# Voltmeter_Before.net
KiCad netlist of a schematic drawn in Altium Designer
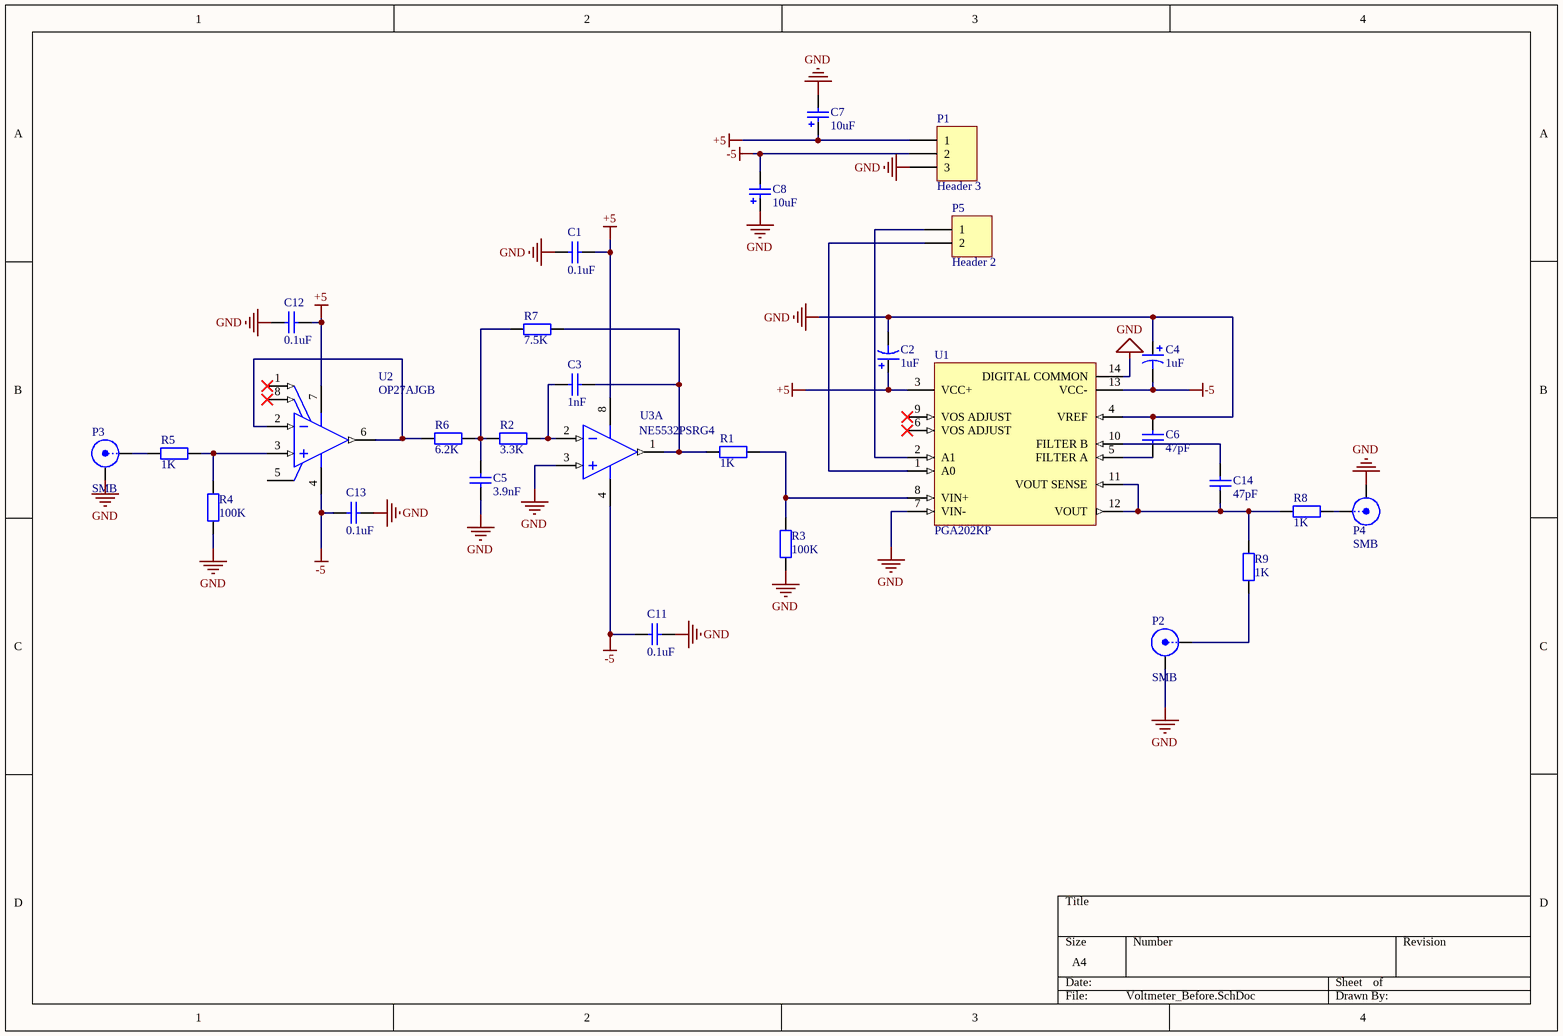
[diagram p0: Voltmeter_Before.SchDoc]

(export (version "E")
  (design (tool "Eeschema 10.0.6"))
  (components
    (comp (ref "C1")
      (value "0.1uF")
      (footprint "C0805")
      (description "Capacitor (Semiconductor SIM Model)")
      (fields (field (name "Comment") "Cap Semi") (field (name "PUBLISHER") "Altium Limited"))
      (libsource (lib "Miscellaneous Devices") (part "Cap Semi"))
    )
    (comp (ref "C2")
      (value "1uF")
      (footprint "C0805")
      (description "Polarized Capacitor (Surface Mount)")
      (fields (field (name "Comment") "Cap Pol3") (field (name "PUBLISHER") "Altium Limited"))
      (libsource (lib "Miscellaneous Devices") (part "Cap Pol3"))
    )
    (comp (ref "C3")
      (value "1nF")
      (footprint "C0805")
      (description "Capacitor (Semiconductor SIM Model)")
      (fields (field (name "Comment") "Cap Semi") (field (name "PUBLISHER") "Altium Limited"))
      (libsource (lib "Miscellaneous Devices") (part "Cap Semi"))
    )
    (comp (ref "C4")
      (value "1uF")
      (footprint "C0805")
      (description "Polarized Capacitor (Surface Mount)")
      (fields (field (name "Comment") "Cap Pol3") (field (name "PUBLISHER") "Altium Limited"))
      (libsource (lib "Miscellaneous Devices") (part "Cap Pol3"))
    )
    (comp (ref "C5")
      (value "3.9nF")
      (footprint "C0805")
      (description "Capacitor (Semiconductor SIM Model)")
      (fields (field (name "Comment") "Cap Semi") (field (name "PUBLISHER") "Altium Limited"))
      (libsource (lib "Miscellaneous Devices") (part "Cap Semi"))
    )
    (comp (ref "C6")
      (value "47pF")
      (footprint "C0805")
      (description "Capacitor (Semiconductor SIM Model)")
      (fields (field (name "Comment") "Cap Semi") (field (name "PUBLISHER") "Altium Limited"))
      (libsource (lib "Miscellaneous Devices") (part "Cap Semi"))
    )
    (comp (ref "C7")
      (value "10uF")
      (footprint "C0805")
      (description "Polarized Capacitor (Axial)")
      (fields (field (name "Comment") "Cap Pol2") (field (name "PUBLISHER") "Altium Limited"))
      (libsource (lib "Miscellaneous Devices") (part "Cap Pol2"))
    )
    (comp (ref "C8")
      (value "10uF")
      (footprint "C0805")
      (description "Polarized Capacitor (Axial)")
      (fields (field (name "Comment") "Cap Pol2") (field (name "PUBLISHER") "Altium Limited"))
      (libsource (lib "Miscellaneous Devices") (part "Cap Pol2"))
    )
    (comp (ref "C11")
      (value "0.1uF")
      (footprint "C0805")
      (description "Capacitor (Semiconductor SIM Model)")
      (fields (field (name "Comment") "Cap Semi") (field (name "PUBLISHER") "Altium Limited"))
      (libsource (lib "Miscellaneous Devices") (part "Cap Semi"))
    )
    (comp (ref "C12")
      (value "0.1uF")
      (footprint "C0805")
      (description "Capacitor (Semiconductor SIM Model)")
      (fields (field (name "Comment") "Cap Semi") (field (name "PUBLISHER") "Altium Limited"))
      (libsource (lib "Miscellaneous Devices") (part "Cap Semi"))
    )
    (comp (ref "C13")
      (value "0.1uF")
      (footprint "C0805")
      (description "Capacitor (Semiconductor SIM Model)")
      (fields (field (name "Comment") "Cap Semi") (field (name "PUBLISHER") "Altium Limited"))
      (libsource (lib "Miscellaneous Devices") (part "Cap Semi"))
    )
    (comp (ref "C14")
      (value "47pF")
      (footprint "C0805")
      (description "Capacitor (Semiconductor SIM Model)")
      (fields (field (name "Comment") "Cap Semi") (field (name "PUBLISHER") "Altium Limited"))
      (libsource (lib "Miscellaneous Devices") (part "Cap Semi"))
    )
    (comp (ref "P1")
      (value "Header 3")
      (footprint "HDR1X3")
      (description "Header, 3-Pin")
      (fields (field (name "PUBLISHER") "Altium Limited"))
      (libsource (lib "Miscellaneous Connectors") (part "Header 3"))
    )
    (comp (ref "P2")
      (value "SMB")
      (footprint "SMB_V-RJ45")
      (description "SMB Straight Connector")
      (fields (field (name "PUBLISHER") "Altium Limited"))
      (libsource (lib "Miscellaneous Connectors") (part "SMB"))
    )
    (comp (ref "P3")
      (value "SMB")
      (footprint "SMB_V-RJ45")
      (description "SMB Straight Connector")
      (fields (field (name "PUBLISHER") "Altium Limited"))
      (libsource (lib "Miscellaneous Connectors") (part "SMB"))
    )
    (comp (ref "P4")
      (value "SMB")
      (footprint "SMB_V-RJ45")
      (description "SMB Straight Connector")
      (fields (field (name "PUBLISHER") "Altium Limited"))
      (libsource (lib "Miscellaneous Connectors") (part "SMB"))
    )
    (comp (ref "P5")
      (value "Header 2")
      (footprint "HDR1X2")
      (description "Header, 2-Pin")
      (fields (field (name "PUBLISHER") "Altium Limited"))
      (libsource (lib "Miscellaneous Connectors") (part "Header 2"))
    )
    (comp (ref "R1")
      (value "1K")
      (footprint "C0805")
      (description "Resistor")
      (fields (field (name "Comment") "Res2") (field (name "PUBLISHER") "Altium Limited"))
      (libsource (lib "") (part "Res2_1"))
    )
    (comp (ref "R2")
      (value "3.3K")
      (footprint "C0805")
      (description "Resistor")
      (fields (field (name "Comment") "Res2") (field (name "PUBLISHER") "Altium Limited"))
      (libsource (lib "") (part "Res2_1"))
    )
    (comp (ref "R3")
      (value "100K")
      (footprint "C0805")
      (description "Resistor")
      (fields (field (name "Comment") "Res2") (field (name "PUBLISHER") "Altium Limited"))
      (libsource (lib "Miscellaneous Devices") (part "Res2"))
    )
    (comp (ref "R4")
      (value "100K")
      (footprint "C0805")
      (description "Resistor")
      (fields (field (name "Comment") "Res2") (field (name "PUBLISHER") "Altium Limited"))
      (libsource (lib "Miscellaneous Devices") (part "Res2"))
    )
    (comp (ref "R5")
      (value "1K")
      (footprint "C0805")
      (description "Resistor")
      (fields (field (name "Comment") "Res2") (field (name "PUBLISHER") "Altium Limited"))
      (libsource (lib "") (part "Res2_1"))
    )
    (comp (ref "R6")
      (value "6.2K")
      (footprint "C0805")
      (description "Resistor")
      (fields (field (name "Comment") "Res2") (field (name "PUBLISHER") "Altium Limited"))
      (libsource (lib "") (part "Res2_1"))
    )
    (comp (ref "R7")
      (value "7.5K")
      (footprint "C0805")
      (description "Resistor")
      (fields (field (name "Comment") "Res2") (field (name "PUBLISHER") "Altium Limited"))
      (libsource (lib "") (part "Res2_2"))
    )
    (comp (ref "R8")
      (value "1K")
      (footprint "C0805")
      (description "Resistor")
      (fields (field (name "Comment") "Res2") (field (name "PUBLISHER") "Altium Limited"))
      (libsource (lib "") (part "Res2_1"))
    )
    (comp (ref "R9")
      (value "1K")
      (footprint "C0805")
      (description "Resistor")
      (fields (field (name "Comment") "Res2") (field (name "PUBLISHER") "Altium Limited"))
      (libsource (lib "Miscellaneous Devices") (part "Res2"))
    )
    (comp (ref "U1")
      (value "PGA202KP")
      (footprint "TI-N14")
      (fields (field (name "MANUFACTURER") "Texas Instruments"))
      (libsource (lib "TI Amplifiers and Linear PGA-VGA") (part "PGA202KP"))
    )
    (comp (ref "U2")
      (value "OP27AJGB")
      (footprint "TI-JG8")
      (description "Low-Noise Precision High-Speed Operational Amplifier, 8 to 44 V, -55 to 125 degC, 8-pin DIP (JG8)")
      (fields (field (name "MANUFACTURER") "Texas Instruments"))
      (libsource (lib "TI Amplifiers and Linear Operational Amplifier Precision Amplifier Part One") (part "OP27AJGB"))
    )
    (comp (ref "U3")
      (value "NE5532PSRG4")
      (footprint "DIP-8")
      (fields (field (name "MANUFACTURER") "Texas Instruments"))
      (libsource (lib "TI Amplifiers and Linear Operational Amplifier General Purpose") (part "NE5532PSRG4"))
    )
  )
  (nets
    (net (code "1") (name "+5") (class "Default")
      (node (ref "C1") (pin "1") (pinfunction "1_1") (pintype "passive"))
      (node (ref "C12") (pin "2") (pinfunction "2_2") (pintype "passive"))
      (node (ref "C2") (pin "1") (pinfunction "1_1") (pintype "passive"))
      (node (ref "C7") (pin "1") (pinfunction "1_1") (pintype "passive"))
      (node (ref "P1") (pin "1") (pinfunction "1_1") (pintype "passive"))
      (node (ref "U1") (pin "3") (pinfunction "VCC+_3") (pintype "power_in"))
      (node (ref "U2") (pin "7") (pinfunction "VCC+_7") (pintype "power_in"))
      (node (ref "U3") (pin "8") (pinfunction "VCC+_8") (pintype "power_in"))
    )
    (net (code "2") (name "-5") (class "Default")
      (node (ref "C11") (pin "2") (pinfunction "2_2") (pintype "passive"))
      (node (ref "C13") (pin "1") (pinfunction "1_1") (pintype "passive"))
      (node (ref "C4") (pin "2") (pinfunction "2_2") (pintype "passive"))
      (node (ref "C8") (pin "2") (pinfunction "2_2") (pintype "passive"))
      (node (ref "P1") (pin "2") (pinfunction "2_2") (pintype "passive"))
      (node (ref "U1") (pin "13") (pinfunction "VCC-_13") (pintype "power_in"))
      (node (ref "U2") (pin "4") (pinfunction "VCC-_4") (pintype "power_in"))
      (node (ref "U3") (pin "4") (pinfunction "VCC-_4") (pintype "power_in"))
    )
    (net (code "3") (name "GND") (class "Default")
      (node (ref "C1") (pin "2") (pinfunction "2_2") (pintype "passive"))
      (node (ref "C11") (pin "1") (pinfunction "1_1") (pintype "passive"))
      (node (ref "C12") (pin "1") (pinfunction "1_1") (pintype "passive"))
      (node (ref "C13") (pin "2") (pinfunction "2_2") (pintype "passive"))
      (node (ref "C2") (pin "2") (pinfunction "2_2") (pintype "passive"))
      (node (ref "C4") (pin "1") (pinfunction "1_1") (pintype "passive"))
      (node (ref "C5") (pin "1") (pinfunction "1_1") (pintype "passive"))
      (node (ref "C6") (pin "2") (pinfunction "2_2") (pintype "passive"))
      (node (ref "C7") (pin "2") (pinfunction "2_2") (pintype "passive"))
      (node (ref "C8") (pin "1") (pinfunction "1_1") (pintype "passive"))
      (node (ref "P1") (pin "3") (pinfunction "3_3") (pintype "passive"))
      (node (ref "P2") (pin "2") (pinfunction "Y_2") (pintype "passive"))
      (node (ref "P3") (pin "2") (pinfunction "Y_2") (pintype "passive"))
      (node (ref "P4") (pin "2") (pinfunction "Y_2") (pintype "passive"))
      (node (ref "R3") (pin "1") (pinfunction "1_1") (pintype "passive"))
      (node (ref "R4") (pin "1") (pinfunction "1_1") (pintype "passive"))
      (node (ref "U1") (pin "14") (pinfunction "DIGITAL_COMMON_14") (pintype "power_in"))
      (node (ref "U1") (pin "4") (pinfunction "VREF_4") (pintype "input"))
      (node (ref "U1") (pin "7") (pinfunction "VIN-_7") (pintype "input"))
      (node (ref "U3") (pin "3") (pinfunction "IN1+_3") (pintype "input"))
    )
    (net (code "4") (name "Net-(C5-Pad2)") (class "Default")
      (node (ref "C5") (pin "2") (pinfunction "2_2") (pintype "passive"))
      (node (ref "R2") (pin "1") (pinfunction "1_1") (pintype "passive"))
      (node (ref "R6") (pin "2") (pinfunction "2_2") (pintype "passive"))
      (node (ref "R7") (pin "2") (pinfunction "2_2") (pintype "passive"))
    )
    (net (code "5") (name "Net-(P2-X)") (class "Default")
      (node (ref "P2") (pin "1") (pinfunction "X_1") (pintype "passive"))
      (node (ref "R9") (pin "1") (pinfunction "1_1") (pintype "passive"))
    )
    (net (code "6") (name "Net-(P3-X)") (class "Default")
      (node (ref "P3") (pin "1") (pinfunction "X_1") (pintype "passive"))
      (node (ref "R5") (pin "1") (pinfunction "1_1") (pintype "passive"))
    )
    (net (code "7") (name "Net-(P4-X)") (class "Default")
      (node (ref "P4") (pin "1") (pinfunction "X_1") (pintype "passive"))
      (node (ref "R8") (pin "2") (pinfunction "2_2") (pintype "passive"))
    )
    (net (code "8") (name "Net-(U1-A0)") (class "Default")
      (node (ref "P5") (pin "2") (pinfunction "2_2") (pintype "passive"))
      (node (ref "U1") (pin "1") (pinfunction "A0_1") (pintype "input"))
    )
    (net (code "9") (name "Net-(U1-A1)") (class "Default")
      (node (ref "P5") (pin "1") (pinfunction "1_1") (pintype "passive"))
      (node (ref "U1") (pin "2") (pinfunction "A1_2") (pintype "input"))
    )
    (net (code "10") (name "Net-(U1-FILTER_A)") (class "Default")
      (node (ref "C6") (pin "1") (pinfunction "1_1") (pintype "passive"))
      (node (ref "U1") (pin "5") (pinfunction "FILTER_A_5") (pintype "input"))
    )
    (net (code "11") (name "Net-(U1-FILTER_B)") (class "Default")
      (node (ref "C14") (pin "2") (pinfunction "2_2") (pintype "passive"))
      (node (ref "U1") (pin "10") (pinfunction "FILTER_B_10") (pintype "input"))
    )
    (net (code "12") (name "Net-(U1-VIN+)") (class "Default")
      (node (ref "R1") (pin "2") (pinfunction "2_2") (pintype "passive"))
      (node (ref "R3") (pin "2") (pinfunction "2_2") (pintype "passive"))
      (node (ref "U1") (pin "8") (pinfunction "VIN+_8") (pintype "input"))
    )
    (net (code "13") (name "Net-(U1-VOUT)") (class "Default")
      (node (ref "C14") (pin "1") (pinfunction "1_1") (pintype "passive"))
      (node (ref "R8") (pin "1") (pinfunction "1_1") (pintype "passive"))
      (node (ref "R9") (pin "2") (pinfunction "2_2") (pintype "passive"))
      (node (ref "U1") (pin "11") (pinfunction "VOUT_SENSE_11") (pintype "input"))
      (node (ref "U1") (pin "12") (pinfunction "VOUT_12") (pintype "output"))
    )
    (net (code "14") (name "Net-(U2-IN+)") (class "Default")
      (node (ref "R4") (pin "2") (pinfunction "2_2") (pintype "passive"))
      (node (ref "R5") (pin "2") (pinfunction "2_2") (pintype "passive"))
      (node (ref "U2") (pin "3") (pinfunction "IN+_3") (pintype "input"))
    )
    (net (code "15") (name "Net-(U2-IN-)") (class "Default")
      (node (ref "R6") (pin "1") (pinfunction "1_1") (pintype "passive"))
      (node (ref "U2") (pin "2") (pinfunction "IN-_2") (pintype "input"))
      (node (ref "U2") (pin "6") (pinfunction "OUT_6") (pintype "output"))
    )
    (net (code "16") (name "Net-(U3A-IN1-)") (class "Default")
      (node (ref "C3") (pin "2") (pinfunction "2_2") (pintype "passive"))
      (node (ref "R2") (pin "2") (pinfunction "2_2") (pintype "passive"))
      (node (ref "U3") (pin "2") (pinfunction "IN1-_2") (pintype "input"))
    )
    (net (code "17") (name "Net-(U3A-OUT1)") (class "Default")
      (node (ref "C3") (pin "1") (pinfunction "1_1") (pintype "passive"))
      (node (ref "R1") (pin "1") (pinfunction "1_1") (pintype "passive"))
      (node (ref "R7") (pin "1") (pinfunction "1_1") (pintype "passive"))
      (node (ref "U3") (pin "1") (pinfunction "OUT1_1") (pintype "output"))
    )
    (net (code "18") (name "unconnected-(U1-VOS_ADJUST-Pad6)") (class "Default")
      (node (ref "U1") (pin "6") (pinfunction "VOS_ADJUST_6") (pintype "input+no_connect"))
    )
    (net (code "19") (name "unconnected-(U1-VOS_ADJUST-Pad9)") (class "Default")
      (node (ref "U1") (pin "9") (pinfunction "VOS_ADJUST_9") (pintype "input+no_connect"))
    )
    (net (code "20") (name "unconnected-(U2-NC-Pad5)") (class "Default")
      (node (ref "U2") (pin "5") (pinfunction "NC_5") (pintype "passive"))
    )
    (net (code "21") (name "unconnected-(U2-VIOTRIM-Pad1)") (class "Default")
      (node (ref "U2") (pin "1") (pinfunction "VIOTRIM_1") (pintype "input+no_connect"))
    )
    (net (code "22") (name "unconnected-(U2-VIOTRIM-Pad8)") (class "Default")
      (node (ref "U2") (pin "8") (pinfunction "VIOTRIM_8") (pintype "input+no_connect"))
    )
  )
)
